# STM32.net
KiCad netlist of a schematic drawn in Altium Designer
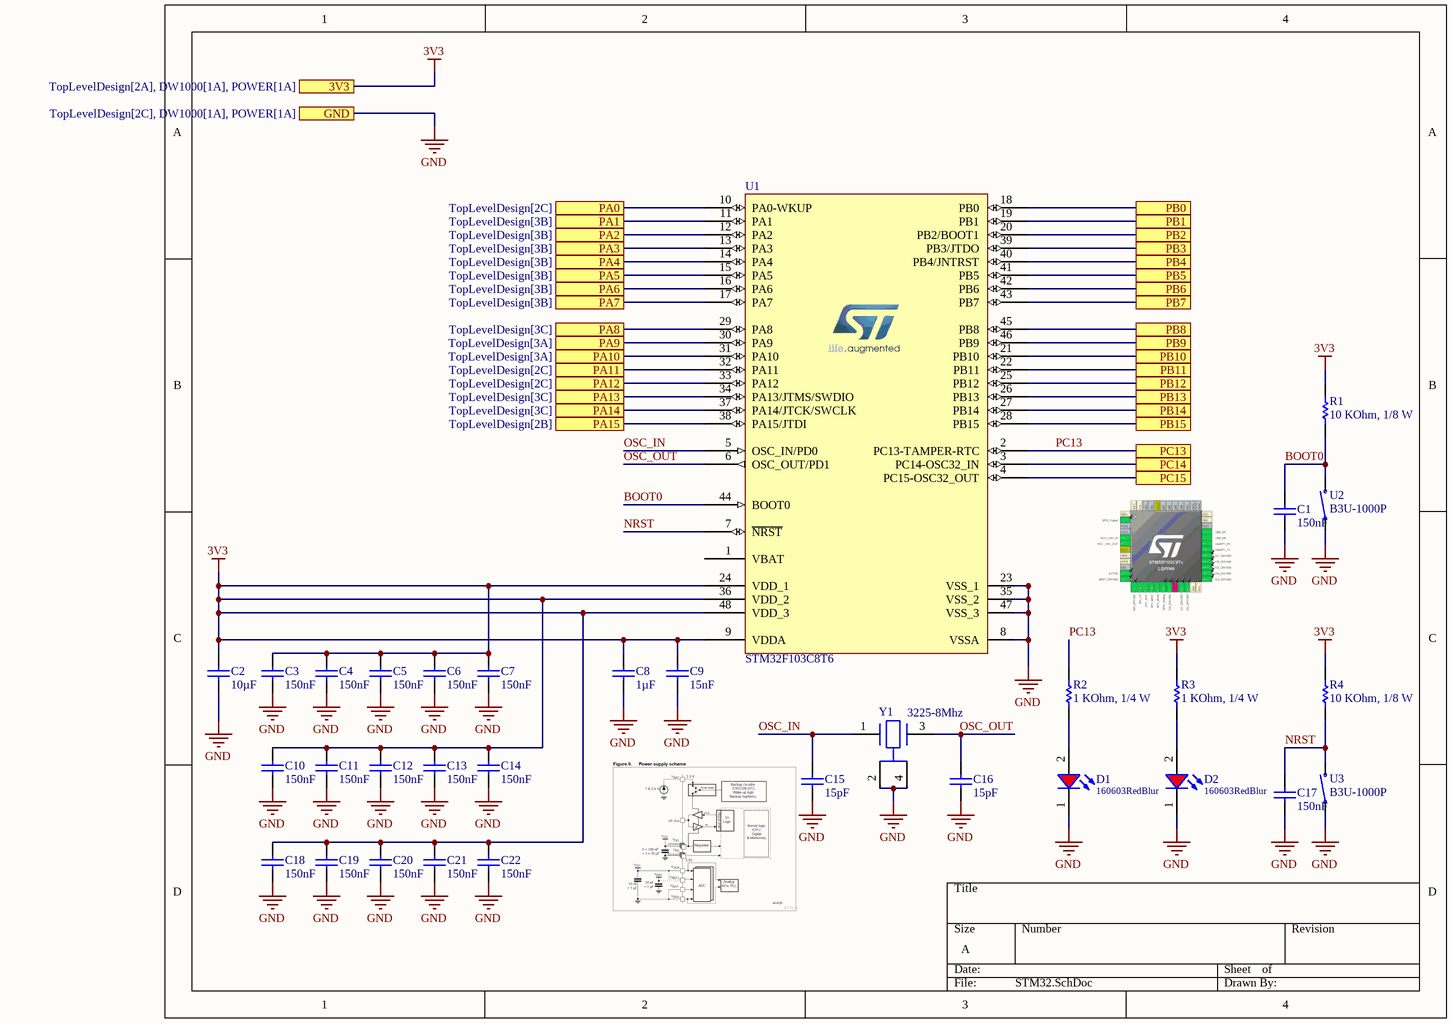
[diagram p0: STM32.SchDoc]

(export (version "E")
  (design (tool "Eeschema 10.0.6"))
  (components
    (comp (ref "C1")
      (value "150nF")
      (footprint "CAP_0805")
      (description "CAP, size 0805, 150 nF, 50 VDC")
      (fields
        (field (name "TOLERANCE") "10%")
        (field (name "Comment") "0108051541050")
        (field (name "SOURCE") "Capacitor_0805_10_percent.SchLib")
      )
      (libsource (lib "Tin Tran") (part "0108056841050"))
    )
    (comp (ref "C2")
      (value "10µF")
      (footprint "CAP_0805")
      (description "CAP, size 0805, 10 uF, 16 VDC")
      (fields
        (field (name "TOLERANCE") "10%")
        (field (name "Comment") "0108051061016")
        (field (name "SOURCE") "Capacitor_0805_10_percent.SchLib")
      )
      (libsource (lib "Tin Tran") (part "0108056841050"))
    )
    (comp (ref "C3")
      (value "150nF")
      (footprint "CAP_0805")
      (description "CAP, size 0805, 150 nF, 50 VDC")
      (fields
        (field (name "TOLERANCE") "10%")
        (field (name "Comment") "0108051541050")
        (field (name "SOURCE") "Capacitor_0805_10_percent.SchLib")
      )
      (libsource (lib "Tin Tran") (part "0108056841050"))
    )
    (comp (ref "C4")
      (value "150nF")
      (footprint "CAP_0805")
      (description "CAP, size 0805, 150 nF, 50 VDC")
      (fields
        (field (name "TOLERANCE") "10%")
        (field (name "Comment") "0108051541050")
        (field (name "SOURCE") "Capacitor_0805_10_percent.SchLib")
      )
      (libsource (lib "Tin Tran") (part "0108056841050"))
    )
    (comp (ref "C5")
      (value "150nF")
      (footprint "CAP_0805")
      (description "CAP, size 0805, 150 nF, 50 VDC")
      (fields
        (field (name "TOLERANCE") "10%")
        (field (name "Comment") "0108051541050")
        (field (name "SOURCE") "Capacitor_0805_10_percent.SchLib")
      )
      (libsource (lib "Tin Tran") (part "0108056841050"))
    )
    (comp (ref "C6")
      (value "150nF")
      (footprint "CAP_0805")
      (description "CAP, size 0805, 150 nF, 50 VDC")
      (fields
        (field (name "TOLERANCE") "10%")
        (field (name "Comment") "0108051541050")
        (field (name "SOURCE") "Capacitor_0805_10_percent.SchLib")
      )
      (libsource (lib "Tin Tran") (part "0108056841050"))
    )
    (comp (ref "C7")
      (value "150nF")
      (footprint "CAP_0805")
      (description "CAP, size 0805, 150 nF, 50 VDC")
      (fields
        (field (name "TOLERANCE") "10%")
        (field (name "Comment") "0108051541050")
        (field (name "SOURCE") "Capacitor_0805_10_percent.SchLib")
      )
      (libsource (lib "Tin Tran") (part "0108056841050"))
    )
    (comp (ref "C8")
      (value "1µF")
      (footprint "CAP_0805")
      (description "CAP, size 0805, 1 uF, 16 VDC")
      (fields
        (field (name "TOLERANCE") "10%")
        (field (name "Comment") "0108051051016")
        (field (name "SOURCE") "Capacitor_0805_10_percent.SchLib")
      )
      (libsource (lib "Tin Tran") (part "0108056841050"))
    )
    (comp (ref "C9")
      (value "15nF")
      (footprint "CAP_0805")
      (description "CAP, size 0805, 15 nF, 50 VDC")
      (fields
        (field (name "TOLERANCE") "5%")
        (field (name "Comment") "0108051531050")
        (field (name "SOURCE") "Capacitor_0805_5_percent.SchLib")
      )
      (libsource (lib "Tin Tran") (part "0108058281050"))
    )
    (comp (ref "C10")
      (value "150nF")
      (footprint "CAP_0805")
      (description "CAP, size 0805, 150 nF, 50 VDC")
      (fields
        (field (name "TOLERANCE") "10%")
        (field (name "Comment") "0108051541050")
        (field (name "SOURCE") "Capacitor_0805_10_percent.SchLib")
      )
      (libsource (lib "Tin Tran") (part "0108056841050"))
    )
    (comp (ref "C11")
      (value "150nF")
      (footprint "CAP_0805")
      (description "CAP, size 0805, 150 nF, 50 VDC")
      (fields
        (field (name "TOLERANCE") "10%")
        (field (name "Comment") "0108051541050")
        (field (name "SOURCE") "Capacitor_0805_10_percent.SchLib")
      )
      (libsource (lib "Tin Tran") (part "0108056841050"))
    )
    (comp (ref "C12")
      (value "150nF")
      (footprint "CAP_0805")
      (description "CAP, size 0805, 150 nF, 50 VDC")
      (fields
        (field (name "TOLERANCE") "10%")
        (field (name "Comment") "0108051541050")
        (field (name "SOURCE") "Capacitor_0805_10_percent.SchLib")
      )
      (libsource (lib "Tin Tran") (part "0108056841050"))
    )
    (comp (ref "C13")
      (value "150nF")
      (footprint "CAP_0805")
      (description "CAP, size 0805, 150 nF, 50 VDC")
      (fields
        (field (name "TOLERANCE") "10%")
        (field (name "Comment") "0108051541050")
        (field (name "SOURCE") "Capacitor_0805_10_percent.SchLib")
      )
      (libsource (lib "Tin Tran") (part "0108056841050"))
    )
    (comp (ref "C14")
      (value "150nF")
      (footprint "CAP_0805")
      (description "CAP, size 0805, 150 nF, 50 VDC")
      (fields
        (field (name "TOLERANCE") "10%")
        (field (name "Comment") "0108051541050")
        (field (name "SOURCE") "Capacitor_0805_10_percent.SchLib")
      )
      (libsource (lib "Tin Tran") (part "0108056841050"))
    )
    (comp (ref "C15")
      (value "15pF")
      (footprint "CAP_0603")
      (description "CAP, size 0603, 15 pF, 50 VDC")
      (fields
        (field (name "TOLERANCE") "5%")
        (field (name "Comment") "0106031500550")
        (field (name "SOURCE") "Capacitor_0603_5_percent.SchLib")
      )
      (libsource (lib "Tin Tran") (part "0106036820550"))
    )
    (comp (ref "C16")
      (value "15pF")
      (footprint "CAP_0603")
      (description "CAP, size 0603, 15 pF, 50 VDC")
      (fields
        (field (name "TOLERANCE") "5%")
        (field (name "Comment") "0106031500550")
        (field (name "SOURCE") "Capacitor_0603_5_percent.SchLib")
      )
      (libsource (lib "Tin Tran") (part "0106036820550"))
    )
    (comp (ref "C17")
      (value "150nF")
      (footprint "CAP_0805")
      (description "CAP, size 0805, 150 nF, 50 VDC")
      (fields
        (field (name "TOLERANCE") "10%")
        (field (name "Comment") "0108051541050")
        (field (name "SOURCE") "Capacitor_0805_10_percent.SchLib")
      )
      (libsource (lib "Tin Tran") (part "0108056841050"))
    )
    (comp (ref "C18")
      (value "150nF")
      (footprint "CAP_0805")
      (description "CAP, size 0805, 150 nF, 50 VDC")
      (fields
        (field (name "TOLERANCE") "10%")
        (field (name "Comment") "0108051541050")
        (field (name "SOURCE") "Capacitor_0805_10_percent.SchLib")
      )
      (libsource (lib "Tin Tran") (part "0108056841050"))
    )
    (comp (ref "C19")
      (value "150nF")
      (footprint "CAP_0805")
      (description "CAP, size 0805, 150 nF, 50 VDC")
      (fields
        (field (name "TOLERANCE") "10%")
        (field (name "Comment") "0108051541050")
        (field (name "SOURCE") "Capacitor_0805_10_percent.SchLib")
      )
      (libsource (lib "Tin Tran") (part "0108056841050"))
    )
    (comp (ref "C20")
      (value "150nF")
      (footprint "CAP_0805")
      (description "CAP, size 0805, 150 nF, 50 VDC")
      (fields
        (field (name "TOLERANCE") "10%")
        (field (name "Comment") "0108051541050")
        (field (name "SOURCE") "Capacitor_0805_10_percent.SchLib")
      )
      (libsource (lib "Tin Tran") (part "0108056841050"))
    )
    (comp (ref "C21")
      (value "150nF")
      (footprint "CAP_0805")
      (description "CAP, size 0805, 150 nF, 50 VDC")
      (fields
        (field (name "TOLERANCE") "10%")
        (field (name "Comment") "0108051541050")
        (field (name "SOURCE") "Capacitor_0805_10_percent.SchLib")
      )
      (libsource (lib "Tin Tran") (part "0108056841050"))
    )
    (comp (ref "C22")
      (value "150nF")
      (footprint "CAP_0805")
      (description "CAP, size 0805, 150 nF, 50 VDC")
      (fields
        (field (name "TOLERANCE") "10%")
        (field (name "Comment") "0108051541050")
        (field (name "SOURCE") "Capacitor_0805_10_percent.SchLib")
      )
      (libsource (lib "Tin Tran") (part "0108056841050"))
    )
    (comp (ref "D1")
      (value "160603RedBlur")
      (footprint "WL-SMCW_0603_H=0.7mm")
      (description "WL-SMCW SMT Mono-color Chip LED Blur, size 0603, Red, 2V, 140deg")
      (libsource (lib "Tin Tran") (part "160603RedClear"))
    )
    (comp (ref "D2")
      (value "160603RedBlur")
      (footprint "WL-SMCW_0603_H=0.7mm")
      (description "WL-SMCW SMT Mono-color Chip LED Blur, size 0603, Red, 2V, 140deg")
      (libsource (lib "Tin Tran") (part "160603RedClear"))
    )
    (comp (ref "R1")
      (value "10 KOhm, 1/8 W")
      (footprint "RESISTOR_0805")
      (description "RES, size 0805, 10 KOhm, 1/8 W")
      (fields (field (name "Comment") "0008051035"))
      (libsource (lib "Tin Tran") (part "0008052035_1"))
    )
    (comp (ref "R2")
      (value "1 KOhm, 1/4 W")
      (footprint "resistor_0603")
      (description "RES, size 0603, 1 KOhm, 1/4 W")
      (fields (field (name "Comment") "0006031021"))
      (libsource (lib "Tin Tran") (part "00060371541"))
    )
    (comp (ref "R3")
      (value "1 KOhm, 1/4 W")
      (footprint "resistor_0603")
      (description "RES, size 0603, 1 KOhm, 1/4 W")
      (fields (field (name "Comment") "0006031021"))
      (libsource (lib "Tin Tran") (part "00060371541"))
    )
    (comp (ref "R4")
      (value "10 KOhm, 1/8 W")
      (footprint "RESISTOR_0805")
      (description "RES, size 0805, 10 KOhm, 1/8 W")
      (fields (field (name "Comment") "0008051035"))
      (libsource (lib "Tin Tran") (part "0008052035_1"))
    )
    (comp (ref "U1")
      (value "STM32F103C8T6")
      (footprint "STM32F103C8T6")
      (description "ARM Microcontrollers - MCU 32BIT Cortex M3 64KB 20KB RAM 2X12 ADC")
      (fields (field (name "MANUFACTURER") "STM"))
      (libsource (lib "Tin Tran") (part "STM32F103C8T6"))
    )
    (comp (ref "U2")
      (value "B3U-1000P")
      (footprint "SODFL4025X160N")
      (description "Switch Tactile N.O. SPST Round Button Gull Wing 0.05A 12VDC 1.5N SMD T/R")
      (fields (field (name "MP") "B3U1000P") (field (name "MF") "Omron"))
      (libsource (lib "Tin Tran") (part "B3U-1000P"))
    )
    (comp (ref "U3")
      (value "B3U-1000P")
      (footprint "SODFL4025X160N")
      (description "Switch Tactile N.O. SPST Round Button Gull Wing 0.05A 12VDC 1.5N SMD T/R")
      (fields (field (name "MP") "B3U1000P") (field (name "MF") "Omron"))
      (libsource (lib "Tin Tran") (part "B3U-1000P"))
    )
    (comp (ref "Y1")
      (value "3225-8Mhz")
      (footprint "FP-NX3225SA-MFG")
      (description "CRYSTAL 8MHZ 8PF SMD")
      (fields (field (name "TOLERANCE") "15ppm") (field (name "MANUFACTURER") "NDK"))
      (libsource (lib "Tin Tran") (part "CMP-200220-000002-1"))
    )
  )
  (nets
    (net (code "1") (name "/BOOT0") (class "Default")
      (node (ref "C1") (pin "1") (pinfunction "1_1") (pintype "passive"))
      (node (ref "R1") (pin "1") (pinfunction "1_1") (pintype "passive"))
      (node (ref "U1") (pin "44") (pinfunction "BOOT0_44") (pintype "input"))
      (node (ref "U2") (pin "2") (pinfunction "2_2") (pintype "passive"))
    )
    (net (code "2") (name "/NRST") (class "Default")
      (node (ref "C17") (pin "1") (pinfunction "1_1") (pintype "passive"))
      (node (ref "R4") (pin "1") (pinfunction "1_1") (pintype "passive"))
      (node (ref "U1") (pin "7") (pinfunction "~{NRST}_7") (pintype "bidirectional"))
      (node (ref "U3") (pin "2") (pinfunction "2_2") (pintype "passive"))
    )
    (net (code "3") (name "/OSC_IN") (class "Default")
      (node (ref "C15") (pin "2") (pinfunction "2_2") (pintype "passive"))
      (node (ref "U1") (pin "5") (pinfunction "OSC_IN/PD0_5") (pintype "input"))
      (node (ref "Y1") (pin "1") (pinfunction "1_1") (pintype "passive"))
    )
    (net (code "4") (name "/OSC_OUT") (class "Default")
      (node (ref "C16") (pin "2") (pinfunction "2_2") (pintype "passive"))
      (node (ref "U1") (pin "6") (pinfunction "OSC_OUT/PD1_6") (pintype "output"))
      (node (ref "Y1") (pin "3") (pinfunction "3_3") (pintype "passive"))
    )
    (net (code "5") (name "/PA0") (class "Default")
      (node (ref "U1") (pin "10") (pinfunction "PA0-WKUP_10") (pintype "bidirectional"))
    )
    (net (code "6") (name "/PA1") (class "Default")
      (node (ref "U1") (pin "11") (pinfunction "PA1_11") (pintype "bidirectional"))
    )
    (net (code "7") (name "/PA2") (class "Default")
      (node (ref "U1") (pin "12") (pinfunction "PA2_12") (pintype "bidirectional"))
    )
    (net (code "8") (name "/PA3") (class "Default")
      (node (ref "U1") (pin "13") (pinfunction "PA3_13") (pintype "bidirectional"))
    )
    (net (code "9") (name "/PA4") (class "Default")
      (node (ref "U1") (pin "14") (pinfunction "PA4_14") (pintype "bidirectional"))
    )
    (net (code "10") (name "/PA5") (class "Default")
      (node (ref "U1") (pin "15") (pinfunction "PA5_15") (pintype "bidirectional"))
    )
    (net (code "11") (name "/PA6") (class "Default")
      (node (ref "U1") (pin "16") (pinfunction "PA6_16") (pintype "bidirectional"))
    )
    (net (code "12") (name "/PA7") (class "Default")
      (node (ref "U1") (pin "17") (pinfunction "PA7_17") (pintype "bidirectional"))
    )
    (net (code "13") (name "/PA8") (class "Default")
      (node (ref "U1") (pin "29") (pinfunction "PA8_29") (pintype "bidirectional"))
    )
    (net (code "14") (name "/PA9") (class "Default")
      (node (ref "U1") (pin "30") (pinfunction "PA9_30") (pintype "bidirectional"))
    )
    (net (code "15") (name "/PA10") (class "Default")
      (node (ref "U1") (pin "31") (pinfunction "PA10_31") (pintype "bidirectional"))
    )
    (net (code "16") (name "/PA11") (class "Default")
      (node (ref "U1") (pin "32") (pinfunction "PA11_32") (pintype "bidirectional"))
    )
    (net (code "17") (name "/PA12") (class "Default")
      (node (ref "U1") (pin "33") (pinfunction "PA12_33") (pintype "bidirectional"))
    )
    (net (code "18") (name "/PA13") (class "Default")
      (node (ref "U1") (pin "34") (pinfunction "PA13/JTMS/SWDIO_34") (pintype "bidirectional"))
    )
    (net (code "19") (name "/PA14") (class "Default")
      (node (ref "U1") (pin "37") (pinfunction "PA14/JTCK/SWCLK_37") (pintype "bidirectional"))
    )
    (net (code "20") (name "/PA15") (class "Default")
      (node (ref "U1") (pin "38") (pinfunction "PA15/JTDI_38") (pintype "bidirectional"))
    )
    (net (code "21") (name "/PB0") (class "Default")
      (node (ref "U1") (pin "18") (pinfunction "PB0_18") (pintype "bidirectional"))
    )
    (net (code "22") (name "/PB1") (class "Default")
      (node (ref "U1") (pin "19") (pinfunction "PB1_19") (pintype "bidirectional"))
    )
    (net (code "23") (name "/PB2") (class "Default")
      (node (ref "U1") (pin "20") (pinfunction "PB2/BOOT1_20") (pintype "bidirectional"))
    )
    (net (code "24") (name "/PB3") (class "Default")
      (node (ref "U1") (pin "39") (pinfunction "PB3/JTDO_39") (pintype "bidirectional"))
    )
    (net (code "25") (name "/PB4") (class "Default")
      (node (ref "U1") (pin "40") (pinfunction "PB4/JNTRST_40") (pintype "bidirectional"))
    )
    (net (code "26") (name "/PB5") (class "Default")
      (node (ref "U1") (pin "41") (pinfunction "PB5_41") (pintype "bidirectional"))
    )
    (net (code "27") (name "/PB6") (class "Default")
      (node (ref "U1") (pin "42") (pinfunction "PB6_42") (pintype "bidirectional"))
    )
    (net (code "28") (name "/PB7") (class "Default")
      (node (ref "U1") (pin "43") (pinfunction "PB7_43") (pintype "bidirectional"))
    )
    (net (code "29") (name "/PB8") (class "Default")
      (node (ref "U1") (pin "45") (pinfunction "PB8_45") (pintype "bidirectional"))
    )
    (net (code "30") (name "/PB9") (class "Default")
      (node (ref "U1") (pin "46") (pinfunction "PB9_46") (pintype "bidirectional"))
    )
    (net (code "31") (name "/PB10") (class "Default")
      (node (ref "U1") (pin "21") (pinfunction "PB10_21") (pintype "bidirectional"))
    )
    (net (code "32") (name "/PB11") (class "Default")
      (node (ref "U1") (pin "22") (pinfunction "PB11_22") (pintype "bidirectional"))
    )
    (net (code "33") (name "/PB12") (class "Default")
      (node (ref "U1") (pin "25") (pinfunction "PB12_25") (pintype "bidirectional"))
    )
    (net (code "34") (name "/PB13") (class "Default")
      (node (ref "U1") (pin "26") (pinfunction "PB13_26") (pintype "bidirectional"))
    )
    (net (code "35") (name "/PB14") (class "Default")
      (node (ref "U1") (pin "27") (pinfunction "PB14_27") (pintype "bidirectional"))
    )
    (net (code "36") (name "/PB15") (class "Default")
      (node (ref "U1") (pin "28") (pinfunction "PB15_28") (pintype "bidirectional"))
    )
    (net (code "37") (name "/PC13") (class "Default")
      (node (ref "R2") (pin "2") (pinfunction "2_2") (pintype "passive"))
      (node (ref "U1") (pin "2") (pinfunction "PC13-TAMPER-RTC_2") (pintype "bidirectional"))
    )
    (net (code "38") (name "/PC14") (class "Default")
      (node (ref "U1") (pin "3") (pinfunction "PC14-OSC32_IN_3") (pintype "bidirectional"))
    )
    (net (code "39") (name "/PC15") (class "Default")
      (node (ref "U1") (pin "4") (pinfunction "PC15-OSC32_OUT_4") (pintype "bidirectional"))
    )
    (net (code "40") (name "3V3") (class "Default")
      (node (ref "C10") (pin "2") (pinfunction "2_2") (pintype "passive"))
      (node (ref "C11") (pin "2") (pinfunction "2_2") (pintype "passive"))
      (node (ref "C12") (pin "2") (pinfunction "2_2") (pintype "passive"))
      (node (ref "C13") (pin "2") (pinfunction "2_2") (pintype "passive"))
      (node (ref "C14") (pin "2") (pinfunction "2_2") (pintype "passive"))
      (node (ref "C18") (pin "2") (pinfunction "2_2") (pintype "passive"))
      (node (ref "C19") (pin "2") (pinfunction "2_2") (pintype "passive"))
      (node (ref "C2") (pin "2") (pinfunction "2_2") (pintype "passive"))
      (node (ref "C20") (pin "2") (pinfunction "2_2") (pintype "passive"))
      (node (ref "C21") (pin "2") (pinfunction "2_2") (pintype "passive"))
      (node (ref "C22") (pin "2") (pinfunction "2_2") (pintype "passive"))
      (node (ref "C3") (pin "2") (pinfunction "2_2") (pintype "passive"))
      (node (ref "C4") (pin "2") (pinfunction "2_2") (pintype "passive"))
      (node (ref "C5") (pin "2") (pinfunction "2_2") (pintype "passive"))
      (node (ref "C6") (pin "2") (pinfunction "2_2") (pintype "passive"))
      (node (ref "C7") (pin "2") (pinfunction "2_2") (pintype "passive"))
      (node (ref "C8") (pin "2") (pinfunction "2_2") (pintype "passive"))
      (node (ref "C9") (pin "2") (pinfunction "2_2") (pintype "passive"))
      (node (ref "R1") (pin "2") (pinfunction "2_2") (pintype "passive"))
      (node (ref "R3") (pin "2") (pinfunction "2_2") (pintype "passive"))
      (node (ref "R4") (pin "2") (pinfunction "2_2") (pintype "passive"))
      (node (ref "U1") (pin "24") (pinfunction "VDD_1_24") (pintype "power_in"))
      (node (ref "U1") (pin "36") (pinfunction "VDD_2_36") (pintype "power_in"))
      (node (ref "U1") (pin "48") (pinfunction "VDD_3_48") (pintype "power_in"))
      (node (ref "U1") (pin "9") (pinfunction "VDDA_9") (pintype "power_in"))
    )
    (net (code "41") (name "GND") (class "Default")
      (node (ref "C1") (pin "2") (pinfunction "2_2") (pintype "passive"))
      (node (ref "C10") (pin "1") (pinfunction "1_1") (pintype "passive"))
      (node (ref "C11") (pin "1") (pinfunction "1_1") (pintype "passive"))
      (node (ref "C12") (pin "1") (pinfunction "1_1") (pintype "passive"))
      (node (ref "C13") (pin "1") (pinfunction "1_1") (pintype "passive"))
      (node (ref "C14") (pin "1") (pinfunction "1_1") (pintype "passive"))
      (node (ref "C15") (pin "1") (pinfunction "1_1") (pintype "passive"))
      (node (ref "C16") (pin "1") (pinfunction "1_1") (pintype "passive"))
      (node (ref "C17") (pin "2") (pinfunction "2_2") (pintype "passive"))
      (node (ref "C18") (pin "1") (pinfunction "1_1") (pintype "passive"))
      (node (ref "C19") (pin "1") (pinfunction "1_1") (pintype "passive"))
      (node (ref "C2") (pin "1") (pinfunction "1_1") (pintype "passive"))
      (node (ref "C20") (pin "1") (pinfunction "1_1") (pintype "passive"))
      (node (ref "C21") (pin "1") (pinfunction "1_1") (pintype "passive"))
      (node (ref "C22") (pin "1") (pinfunction "1_1") (pintype "passive"))
      (node (ref "C3") (pin "1") (pinfunction "1_1") (pintype "passive"))
      (node (ref "C4") (pin "1") (pinfunction "1_1") (pintype "passive"))
      (node (ref "C5") (pin "1") (pinfunction "1_1") (pintype "passive"))
      (node (ref "C6") (pin "1") (pinfunction "1_1") (pintype "passive"))
      (node (ref "C7") (pin "1") (pinfunction "1_1") (pintype "passive"))
      (node (ref "C8") (pin "1") (pinfunction "1_1") (pintype "passive"))
      (node (ref "C9") (pin "1") (pinfunction "1_1") (pintype "passive"))
      (node (ref "D1") (pin "1") (pinfunction "K_1") (pintype "passive"))
      (node (ref "D2") (pin "1") (pinfunction "K_1") (pintype "passive"))
      (node (ref "U1") (pin "23") (pinfunction "VSS_1_23") (pintype "power_in"))
      (node (ref "U1") (pin "35") (pinfunction "VSS_2_35") (pintype "power_in"))
      (node (ref "U1") (pin "47") (pinfunction "VSS_3_47") (pintype "power_in"))
      (node (ref "U1") (pin "8") (pinfunction "VSSA_8") (pintype "power_in"))
      (node (ref "U2") (pin "1") (pinfunction "1_1") (pintype "passive"))
      (node (ref "U3") (pin "1") (pinfunction "1_1") (pintype "passive"))
      (node (ref "Y1") (pin "2") (pinfunction "GND_2") (pintype "power_in"))
      (node (ref "Y1") (pin "4") (pinfunction "GND_4") (pintype "power_in"))
    )
    (net (code "42") (name "Net-(D1-A)") (class "Default")
      (node (ref "D1") (pin "2") (pinfunction "A_2") (pintype "passive"))
      (node (ref "R2") (pin "1") (pinfunction "1_1") (pintype "passive"))
    )
    (net (code "43") (name "Net-(D2-A)") (class "Default")
      (node (ref "D2") (pin "2") (pinfunction "A_2") (pintype "passive"))
      (node (ref "R3") (pin "1") (pinfunction "1_1") (pintype "passive"))
    )
    (net (code "44") (name "unconnected-(U1-VBAT-Pad1)") (class "Default")
      (node (ref "U1") (pin "1") (pinfunction "VBAT_1") (pintype "power_in"))
    )
  )
)
